# IC.net
KiCad netlist of a schematic drawn in Altium Designer
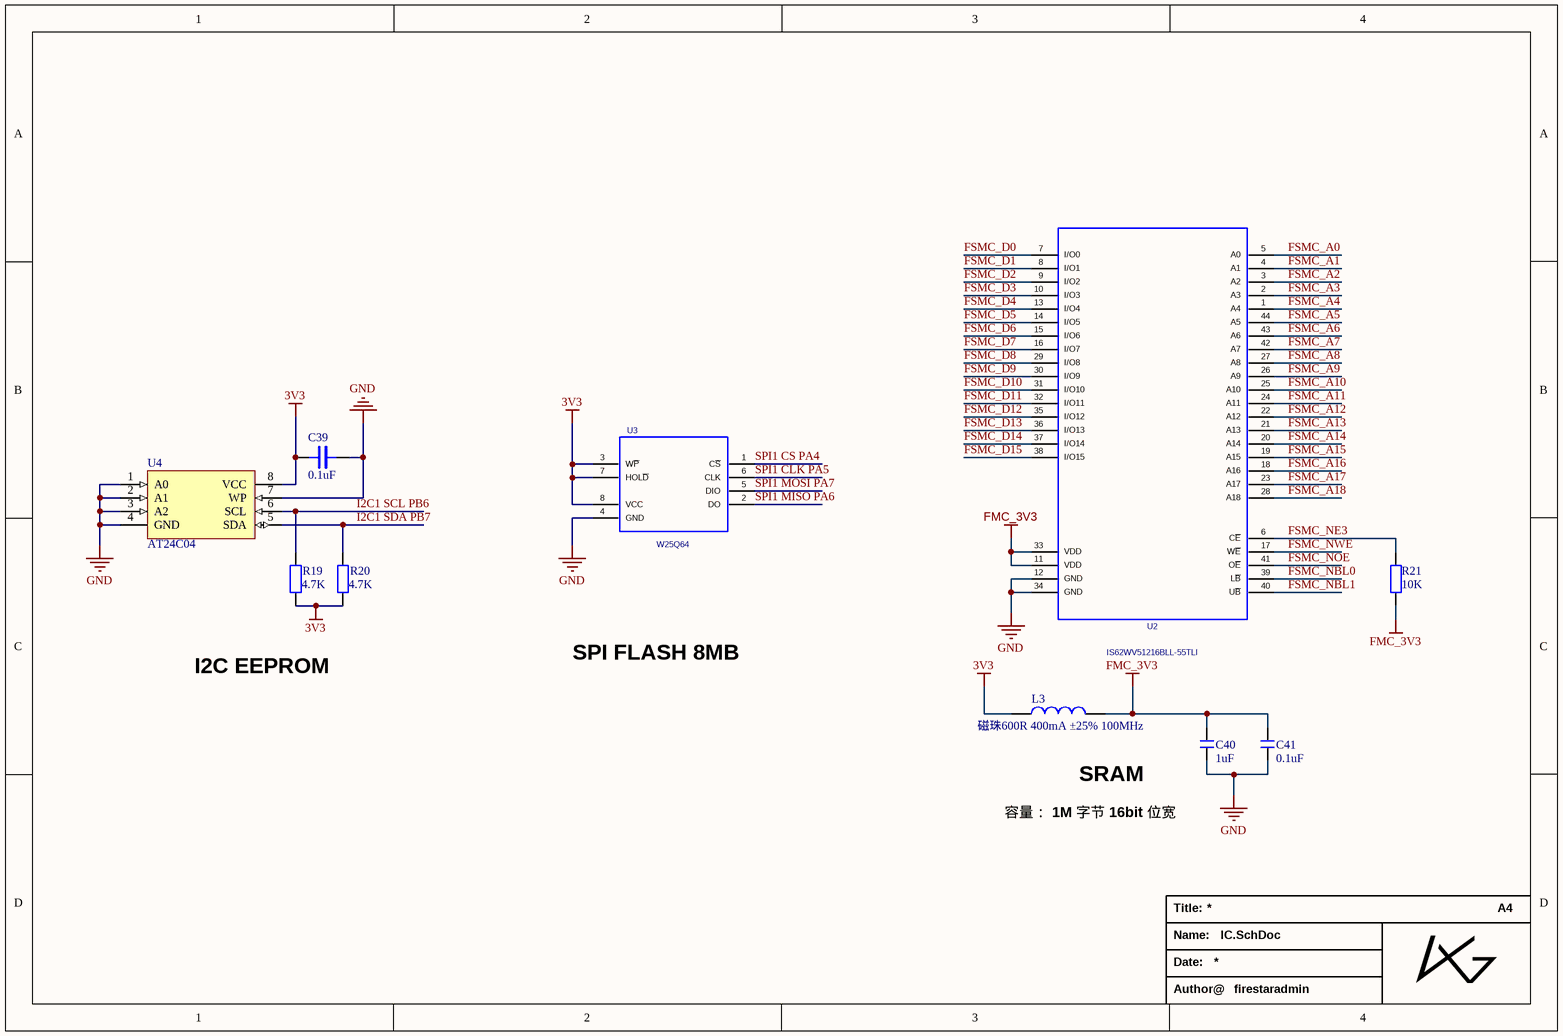
[diagram p0: IC.SchDoc]

(export (version "E")
  (design (tool "Eeschema 10.0.6"))
  (components
    (comp (ref "C39")
      (value "0.1uF")
      (footprint "C 0603_M")
      (description "Capacitor")
      (libsource (lib "General") (part "CAP"))
    )
    (comp (ref "C40")
      (value "1uF")
      (footprint "C 0603_M")
      (description "无极性贴片电容")
      (fields (field (name "版权归属") "源创客"))
      (libsource (lib "altium-import") (part "root_1_C_"))
    )
    (comp (ref "C41")
      (value "0.1uF")
      (footprint "C 0603_M")
      (description "无极性贴片电容")
      (fields (field (name "版权归属") "源创客"))
      (libsource (lib "altium-import") (part "root_1_C_"))
    )
    (comp (ref "L3")
      (value "磁珠600R 400mA ±25% 100MHz")
      (footprint "L 0603")
      (description "小功率贴片电感")
      (fields (field (name "版权归属") "源创客"))
      (libsource (lib "altium-import") (part "root_0_L_"))
    )
    (comp (ref "R19")
      (value "4.7K")
      (footprint "R 0603_M")
      (description "Resistor")
      (libsource (lib "General") (part "RES"))
    )
    (comp (ref "R20")
      (value "4.7K")
      (footprint "R 0603_M")
      (description "Resistor")
      (libsource (lib "General") (part "RES"))
    )
    (comp (ref "R21")
      (value "10K")
      (footprint "R 0603_M")
      (description "Resistor")
      (libsource (lib "General") (part "RES"))
    )
    (comp (ref "U2")
      (value "IS62WV51216BLL-55TLI")
      (footprint "TSOP44-0.8MM")
      (description "TSOP-II,2.5V - 3.6V, 512K x 16,55ns")
      (fields (field (name "TOLERANCE") "55ns"))
      (libsource (lib "altium-import") (part "root_0_IS62WV51216BLL-55TLI_"))
    )
    (comp (ref "U3")
      (value "W25Q64")
      (footprint "SOP8W_M")
      (libsource (lib "altium-import") (part "root_0_W25Q64_"))
    )
    (comp (ref "U4")
      (value "AT24C04")
      (footprint "SOP8_M")
      (description "EEPROM")
      (libsource (lib "General") (part "AT24Cxx"))
    )
  )
  (nets
    (net (code "1") (name "/FSMC_A0") (class "Default")
      (node (ref "U2") (pin "5") (pinfunction "A0_5") (pintype "passive"))
    )
    (net (code "2") (name "/FSMC_A1") (class "Default")
      (node (ref "U2") (pin "4") (pinfunction "A1_4") (pintype "passive"))
    )
    (net (code "3") (name "/FSMC_A2") (class "Default")
      (node (ref "U2") (pin "3") (pinfunction "A2_3") (pintype "passive"))
    )
    (net (code "4") (name "/FSMC_A3") (class "Default")
      (node (ref "U2") (pin "2") (pinfunction "A3_2") (pintype "passive"))
    )
    (net (code "5") (name "/FSMC_A4") (class "Default")
      (node (ref "U2") (pin "1") (pinfunction "A4_1") (pintype "passive"))
    )
    (net (code "6") (name "/FSMC_A5") (class "Default")
      (node (ref "U2") (pin "44") (pinfunction "A5_44") (pintype "passive"))
    )
    (net (code "7") (name "/FSMC_A6") (class "Default")
      (node (ref "U2") (pin "43") (pinfunction "A6_43") (pintype "passive"))
    )
    (net (code "8") (name "/FSMC_A7") (class "Default")
      (node (ref "U2") (pin "42") (pinfunction "A7_42") (pintype "passive"))
    )
    (net (code "9") (name "/FSMC_A8") (class "Default")
      (node (ref "U2") (pin "27") (pinfunction "A8_27") (pintype "passive"))
    )
    (net (code "10") (name "/FSMC_A9") (class "Default")
      (node (ref "U2") (pin "26") (pinfunction "A9_26") (pintype "passive"))
    )
    (net (code "11") (name "/FSMC_A10") (class "Default")
      (node (ref "U2") (pin "25") (pinfunction "A10_25") (pintype "passive"))
    )
    (net (code "12") (name "/FSMC_A11") (class "Default")
      (node (ref "U2") (pin "24") (pinfunction "A11_24") (pintype "passive"))
    )
    (net (code "13") (name "/FSMC_A12") (class "Default")
      (node (ref "U2") (pin "22") (pinfunction "A12_22") (pintype "passive"))
    )
    (net (code "14") (name "/FSMC_A13") (class "Default")
      (node (ref "U2") (pin "21") (pinfunction "A13_21") (pintype "passive"))
    )
    (net (code "15") (name "/FSMC_A14") (class "Default")
      (node (ref "U2") (pin "20") (pinfunction "A14_20") (pintype "passive"))
    )
    (net (code "16") (name "/FSMC_A15") (class "Default")
      (node (ref "U2") (pin "19") (pinfunction "A15_19") (pintype "passive"))
    )
    (net (code "17") (name "/FSMC_A16") (class "Default")
      (node (ref "U2") (pin "18") (pinfunction "A16_18") (pintype "passive"))
    )
    (net (code "18") (name "/FSMC_A17") (class "Default")
      (node (ref "U2") (pin "23") (pinfunction "A17_23") (pintype "passive"))
    )
    (net (code "19") (name "/FSMC_A18") (class "Default")
      (node (ref "U2") (pin "28") (pinfunction "A18_28") (pintype "passive"))
    )
    (net (code "20") (name "/FSMC_D0") (class "Default")
      (node (ref "U2") (pin "7") (pinfunction "I/O0_7") (pintype "passive"))
    )
    (net (code "21") (name "/FSMC_D1") (class "Default")
      (node (ref "U2") (pin "8") (pinfunction "I/O1_8") (pintype "passive"))
    )
    (net (code "22") (name "/FSMC_D2") (class "Default")
      (node (ref "U2") (pin "9") (pinfunction "I/O2_9") (pintype "passive"))
    )
    (net (code "23") (name "/FSMC_D3") (class "Default")
      (node (ref "U2") (pin "10") (pinfunction "I/O3_10") (pintype "passive"))
    )
    (net (code "24") (name "/FSMC_D4") (class "Default")
      (node (ref "U2") (pin "13") (pinfunction "I/O4_13") (pintype "passive"))
    )
    (net (code "25") (name "/FSMC_D5") (class "Default")
      (node (ref "U2") (pin "14") (pinfunction "I/O5_14") (pintype "passive"))
    )
    (net (code "26") (name "/FSMC_D6") (class "Default")
      (node (ref "U2") (pin "15") (pinfunction "I/O6_15") (pintype "passive"))
    )
    (net (code "27") (name "/FSMC_D7") (class "Default")
      (node (ref "U2") (pin "16") (pinfunction "I/O7_16") (pintype "passive"))
    )
    (net (code "28") (name "/FSMC_D8") (class "Default")
      (node (ref "U2") (pin "29") (pinfunction "I/O8_29") (pintype "passive"))
    )
    (net (code "29") (name "/FSMC_D9") (class "Default")
      (node (ref "U2") (pin "30") (pinfunction "I/O9_30") (pintype "passive"))
    )
    (net (code "30") (name "/FSMC_D10") (class "Default")
      (node (ref "U2") (pin "31") (pinfunction "I/O10_31") (pintype "passive"))
    )
    (net (code "31") (name "/FSMC_D11") (class "Default")
      (node (ref "U2") (pin "32") (pinfunction "I/O11_32") (pintype "passive"))
    )
    (net (code "32") (name "/FSMC_D12") (class "Default")
      (node (ref "U2") (pin "35") (pinfunction "I/O12_35") (pintype "passive"))
    )
    (net (code "33") (name "/FSMC_D13") (class "Default")
      (node (ref "U2") (pin "36") (pinfunction "I/O13_36") (pintype "passive"))
    )
    (net (code "34") (name "/FSMC_D14") (class "Default")
      (node (ref "U2") (pin "37") (pinfunction "I/O14_37") (pintype "passive"))
    )
    (net (code "35") (name "/FSMC_D15") (class "Default")
      (node (ref "U2") (pin "38") (pinfunction "I/O15_38") (pintype "passive"))
    )
    (net (code "36") (name "/FSMC_NBL0") (class "Default")
      (node (ref "U2") (pin "39") (pinfunction "L~{B}_39") (pintype "passive"))
    )
    (net (code "37") (name "/FSMC_NBL1") (class "Default")
      (node (ref "U2") (pin "40") (pinfunction "U~{B}_40") (pintype "passive"))
    )
    (net (code "38") (name "/FSMC_NE3") (class "Default")
      (node (ref "R21") (pin "1") (pinfunction "1_1") (pintype "passive"))
      (node (ref "U2") (pin "6") (pinfunction "C~{E}_6") (pintype "passive"))
    )
    (net (code "39") (name "/FSMC_NOE") (class "Default")
      (node (ref "U2") (pin "41") (pinfunction "O~{E}_41") (pintype "passive"))
    )
    (net (code "40") (name "/FSMC_NWE") (class "Default")
      (node (ref "U2") (pin "17") (pinfunction "W~{E}_17") (pintype "passive"))
    )
    (net (code "41") (name "/I2C1 SCL PB6") (class "Default")
      (node (ref "R19") (pin "1") (pinfunction "1_1") (pintype "passive"))
      (node (ref "U4") (pin "6") (pinfunction "SCL_6") (pintype "input"))
    )
    (net (code "42") (name "/I2C1 SDA PB7") (class "Default")
      (node (ref "R20") (pin "1") (pinfunction "1_1") (pintype "passive"))
      (node (ref "U4") (pin "5") (pinfunction "SDA_5") (pintype "bidirectional"))
    )
    (net (code "43") (name "/SPI1 CLK PA5") (class "Default")
      (node (ref "U3") (pin "6") (pinfunction "CLK_6") (pintype "passive"))
    )
    (net (code "44") (name "/SPI1 CS PA4") (class "Default")
      (node (ref "U3") (pin "1") (pinfunction "C~{S}_1") (pintype "passive"))
    )
    (net (code "45") (name "/SPI1 MISO PA6") (class "Default")
      (node (ref "U3") (pin "2") (pinfunction "DO_2") (pintype "passive"))
    )
    (net (code "46") (name "/SPI1 MOSI PA7") (class "Default")
      (node (ref "U3") (pin "5") (pinfunction "DIO_5") (pintype "passive"))
    )
    (net (code "47") (name "3V3") (class "Default")
      (node (ref "C39") (pin "1") (pinfunction "1_1") (pintype "passive"))
      (node (ref "L3") (pin "1") (pinfunction "1_1") (pintype "passive"))
      (node (ref "R19") (pin "2") (pinfunction "2_2") (pintype "passive"))
      (node (ref "R20") (pin "2") (pinfunction "2_2") (pintype "passive"))
      (node (ref "U3") (pin "3") (pinfunction "W~{P}_3") (pintype "passive"))
      (node (ref "U3") (pin "7") (pinfunction "HOL~{D}_7") (pintype "passive"))
      (node (ref "U3") (pin "8") (pinfunction "VCC_8") (pintype "passive"))
      (node (ref "U4") (pin "8") (pinfunction "VCC_8") (pintype "power_in"))
    )
    (net (code "48") (name "FMC_3V3") (class "Default")
      (node (ref "C40") (pin "2") (pinfunction "2_2") (pintype "passive"))
      (node (ref "C41") (pin "2") (pinfunction "2_2") (pintype "passive"))
      (node (ref "L3") (pin "2") (pinfunction "2_2") (pintype "passive"))
      (node (ref "R21") (pin "2") (pinfunction "2_2") (pintype "passive"))
      (node (ref "U2") (pin "11") (pinfunction "VDD_11") (pintype "passive"))
      (node (ref "U2") (pin "33") (pinfunction "VDD_33") (pintype "passive"))
    )
    (net (code "49") (name "GND") (class "Default")
      (node (ref "C39") (pin "2") (pinfunction "2_2") (pintype "passive"))
      (node (ref "C40") (pin "1") (pinfunction "1_1") (pintype "passive"))
      (node (ref "C41") (pin "1") (pinfunction "1_1") (pintype "passive"))
      (node (ref "U2") (pin "12") (pinfunction "GND_12") (pintype "passive"))
      (node (ref "U2") (pin "34") (pinfunction "GND_34") (pintype "passive"))
      (node (ref "U3") (pin "4") (pinfunction "GND_4") (pintype "passive"))
      (node (ref "U4") (pin "1") (pinfunction "A0_1") (pintype "input"))
      (node (ref "U4") (pin "2") (pinfunction "A1_2") (pintype "input"))
      (node (ref "U4") (pin "3") (pinfunction "A2_3") (pintype "input"))
      (node (ref "U4") (pin "4") (pinfunction "GND_4") (pintype "power_in"))
      (node (ref "U4") (pin "7") (pinfunction "WP_7") (pintype "input"))
    )
  )
)
